# PWR_DC_DC_EXAR.net
KiCad netlist of a schematic drawn in Altium Designer
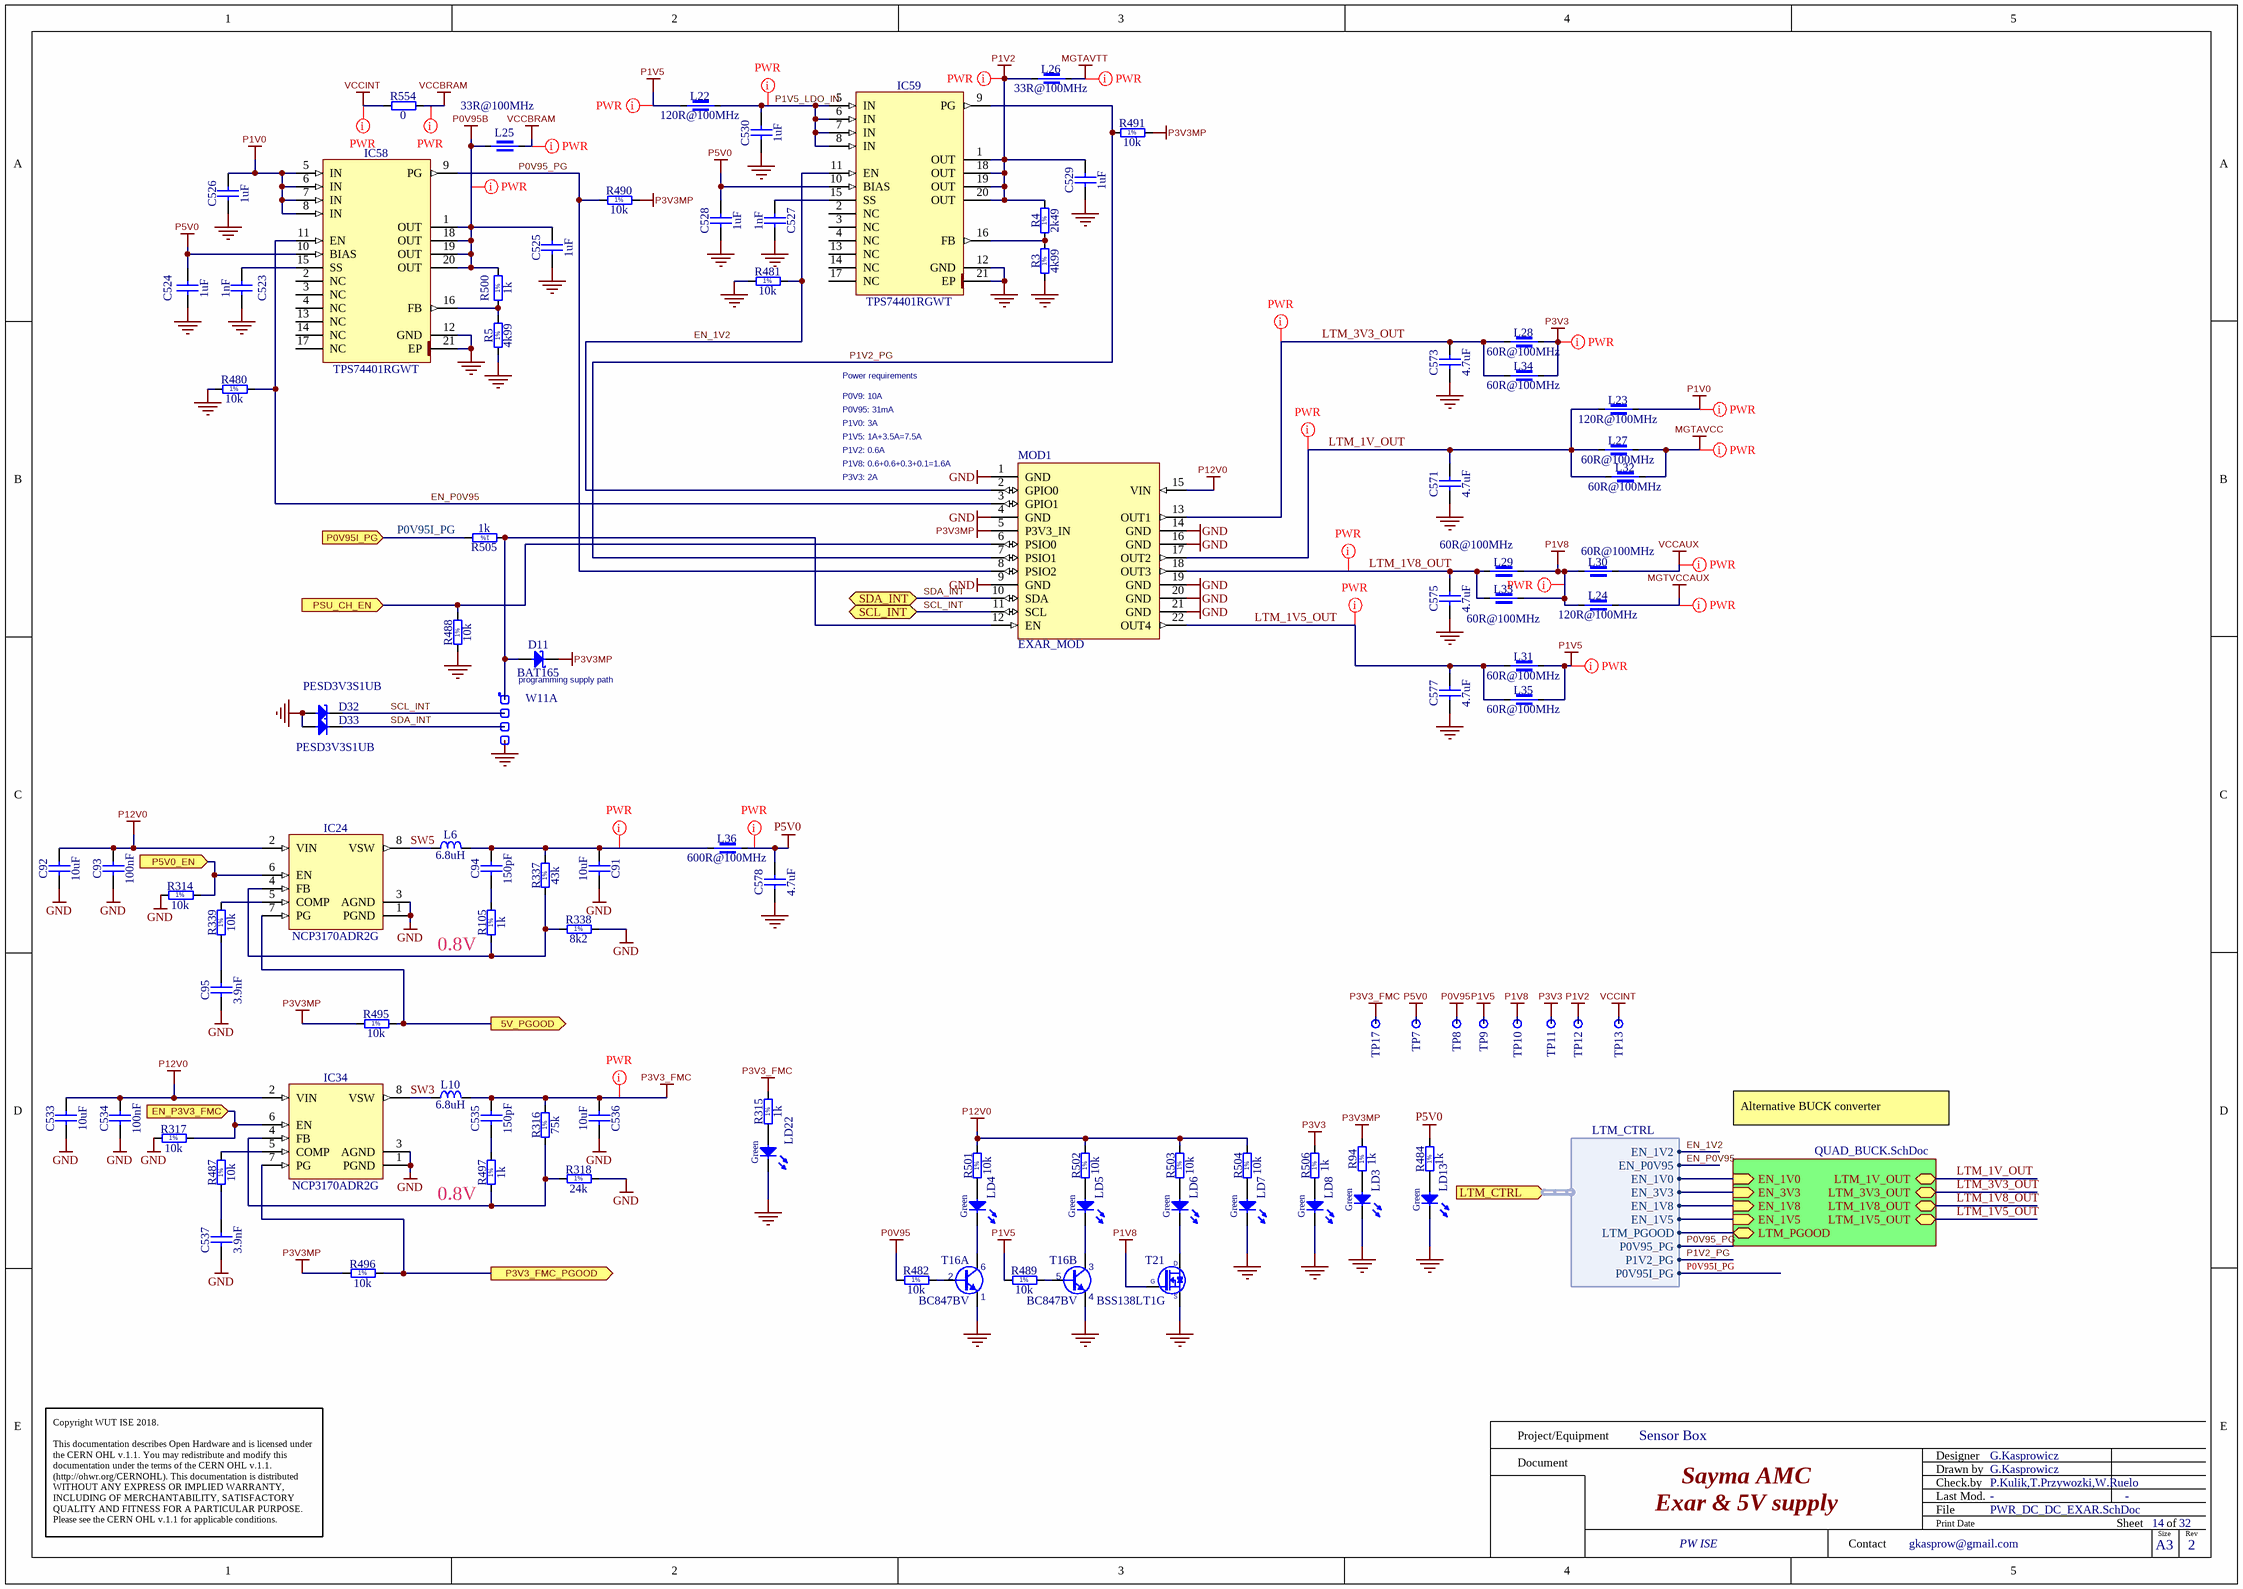
[diagram p0: PWR_DC_DC_EXAR.SchDoc]

(export (version "E")
  (design (tool "Eeschema 10.0.6"))
  (components
    (comp (ref "C91")
      (value "10uF")
      (footprint "CAPC2012X135N")
      (description "Non-polarised capacitor")
      (fields
        (field (name "PART NUMBER") "CC0805_10UF_16V_10%_X5R")
        (field (name "VOLTAGE") "16V")
        (field (name "AUTHOR") "CERN DEM JLC")
      )
      (libsource (lib "Capacitors") (part "Capacitor - non polarized"))
    )
    (comp (ref "C92")
      (value "10uF")
      (footprint "CAPC2012X135N")
      (description "Non-polarised capacitor")
      (fields
        (field (name "PART NUMBER") "CC0805_10UF_16V_10%_X5R")
        (field (name "VOLTAGE") "16V")
        (field (name "AUTHOR") "CERN DEM JLC")
      )
      (libsource (lib "Capacitors") (part "Capacitor - non polarized"))
    )
    (comp (ref "C93")
      (value "100nF")
      (footprint "CAPC1005X55N")
      (description "Non-polarised capacitor")
      (fields
        (field (name "PART NUMBER") "CC0402_100NF_16V_10%_X5R")
        (field (name "VOLTAGE") "16V")
        (field (name "AUTHOR") "CERN DEM JLC")
      )
      (libsource (lib "Capacitors") (part "Capacitor - non polarized"))
    )
    (comp (ref "C94")
      (value "150pF")
      (footprint "CAPC1608X87N")
      (description "Non-polarised capacitor")
      (fields
        (field (name "PART NUMBER") "CC0603_150PF_50V_1%_NP0")
        (field (name "VOLTAGE") "50V")
        (field (name "AUTHOR") "CERN DEM MR")
      )
      (libsource (lib "Capacitors") (part "Capacitor - non polarized"))
    )
    (comp (ref "C95")
      (value "3.9nF")
      (footprint "CAPC1608X87N")
      (description "Non-polarised capacitor")
      (fields
        (field (name "PART NUMBER") "CC0603_3.9NF_50V_5%_X7R")
        (field (name "VOLTAGE") "50V")
        (field (name "AUTHOR") "CERN DEM JLC")
      )
      (libsource (lib "Capacitors") (part "Capacitor - non polarized"))
    )
    (comp (ref "C523")
      (value "1nF")
      (footprint "CAPC1005X55N")
      (description "Non-polarised capacitor")
      (fields
        (field (name "MANUFACTURER PART NUMBER") "CC0402_1NF_50V_10%_X7R")
        (field (name "MANUFACTURER") "GENERIC")
        (field (name "AUTHOR") "CERN DEM JLC")
      )
      (libsource (lib "Capacitors") (part "Capacitor - non polarized"))
    )
    (comp (ref "C524")
      (value "1uF")
      (footprint "CAPC1005X55N")
      (description "Non-polarised capacitor")
      (fields
        (field (name "MANUFACTURER PART NUMBER") "CC0402_1UF_16V_10%_X5R")
        (field (name "MANUFACTURER") "GENERIC")
        (field (name "AUTHOR") "CERN DEM JLC")
      )
      (libsource (lib "Capacitors") (part "Capacitor - non polarized"))
    )
    (comp (ref "C525")
      (value "1uF")
      (footprint "CAPC1005X55N")
      (description "Non-polarised capacitor")
      (fields
        (field (name "MANUFACTURER PART NUMBER") "CC0402_1UF_16V_10%_X5R")
        (field (name "MANUFACTURER") "GENERIC")
        (field (name "AUTHOR") "CERN DEM JLC")
      )
      (libsource (lib "Capacitors") (part "Capacitor - non polarized"))
    )
    (comp (ref "C526")
      (value "1uF")
      (footprint "CAPC1005X55N")
      (description "Non-polarised capacitor")
      (fields
        (field (name "MANUFACTURER PART NUMBER") "CC0402_1UF_16V_10%_X5R")
        (field (name "MANUFACTURER") "GENERIC")
        (field (name "AUTHOR") "CERN DEM JLC")
      )
      (libsource (lib "Capacitors") (part "Capacitor - non polarized"))
    )
    (comp (ref "C527")
      (value "1nF")
      (footprint "CAPC1005X55N")
      (description "Non-polarised capacitor")
      (fields
        (field (name "MANUFACTURER PART NUMBER") "CC0402_1NF_50V_10%_X7R")
        (field (name "MANUFACTURER") "GENERIC")
        (field (name "AUTHOR") "CERN DEM JLC")
      )
      (libsource (lib "Capacitors") (part "Capacitor - non polarized"))
    )
    (comp (ref "C528")
      (value "1uF")
      (footprint "CAPC1005X55N")
      (description "Non-polarised capacitor")
      (fields
        (field (name "MANUFACTURER PART NUMBER") "CC0402_1UF_16V_10%_X5R")
        (field (name "MANUFACTURER") "GENERIC")
        (field (name "AUTHOR") "CERN DEM JLC")
      )
      (libsource (lib "Capacitors") (part "Capacitor - non polarized"))
    )
    (comp (ref "C529")
      (value "1uF")
      (footprint "CAPC1005X55N")
      (description "Non-polarised capacitor")
      (fields
        (field (name "MANUFACTURER PART NUMBER") "CC0402_1UF_16V_10%_X5R")
        (field (name "MANUFACTURER") "GENERIC")
        (field (name "AUTHOR") "CERN DEM JLC")
      )
      (libsource (lib "Capacitors") (part "Capacitor - non polarized"))
    )
    (comp (ref "C530")
      (value "1uF")
      (footprint "CAPC1005X55N")
      (description "Non-polarised capacitor")
      (fields
        (field (name "MANUFACTURER PART NUMBER") "CC0402_1UF_16V_10%_X5R")
        (field (name "MANUFACTURER") "GENERIC")
        (field (name "AUTHOR") "CERN DEM JLC")
      )
      (libsource (lib "Capacitors") (part "Capacitor - non polarized"))
    )
    (comp (ref "C533")
      (value "10uF")
      (footprint "CAPC2012X135N")
      (description "Non-polarised capacitor")
      (fields
        (field (name "PART NUMBER") "CC0805_10UF_16V_10%_X5R")
        (field (name "VOLTAGE") "16V")
        (field (name "AUTHOR") "CERN DEM JLC")
      )
      (libsource (lib "Capacitors") (part "Capacitor - non polarized"))
    )
    (comp (ref "C534")
      (value "100nF")
      (footprint "CAPC1005X55N")
      (description "Non-polarised capacitor")
      (fields
        (field (name "PART NUMBER") "CC0402_100NF_16V_10%_X5R")
        (field (name "VOLTAGE") "16V")
        (field (name "AUTHOR") "CERN DEM JLC")
      )
      (libsource (lib "Capacitors") (part "Capacitor - non polarized"))
    )
    (comp (ref "C535")
      (value "150pF")
      (footprint "CAPC1608X87N")
      (description "Non-polarised capacitor")
      (fields
        (field (name "PART NUMBER") "CC0603_150PF_50V_1%_NP0")
        (field (name "VOLTAGE") "50V")
        (field (name "AUTHOR") "CERN DEM MR")
      )
      (libsource (lib "Capacitors") (part "Capacitor - non polarized"))
    )
    (comp (ref "C536")
      (value "10uF")
      (footprint "CAPC2012X135N")
      (description "Non-polarised capacitor")
      (fields
        (field (name "PART NUMBER") "CC0805_10UF_16V_10%_X5R")
        (field (name "VOLTAGE") "16V")
        (field (name "AUTHOR") "CERN DEM JLC")
      )
      (libsource (lib "Capacitors") (part "Capacitor - non polarized"))
    )
    (comp (ref "C537")
      (value "3.9nF")
      (footprint "CAPC1608X87N")
      (description "Non-polarised capacitor")
      (fields
        (field (name "PART NUMBER") "CC0603_3.9NF_50V_5%_X7R")
        (field (name "VOLTAGE") "50V")
        (field (name "AUTHOR") "CERN DEM JLC")
      )
      (libsource (lib "Capacitors") (part "Capacitor - non polarized"))
    )
    (comp (ref "C571")
      (value "4.7uF")
      (footprint "CAPC1709X95N")
      (description "Non-polarised capacitor")
      (fields
        (field (name "MANUFACTURER PART NUMBER") "CC0603_4.7UF_16V_10%_X5R")
        (field (name "MANUFACTURER") "GENERIC")
        (field (name "AUTHOR") "CERN DEM JLC")
      )
      (libsource (lib "Capacitors") (part "Capacitor - non polarized"))
    )
    (comp (ref "C573")
      (value "4.7uF")
      (footprint "CAPC1709X95N")
      (description "Non-polarised capacitor")
      (fields
        (field (name "MANUFACTURER PART NUMBER") "CC0603_4.7UF_16V_10%_X5R")
        (field (name "MANUFACTURER") "GENERIC")
        (field (name "AUTHOR") "CERN DEM JLC")
      )
      (libsource (lib "Capacitors") (part "Capacitor - non polarized"))
    )
    (comp (ref "C575")
      (value "4.7uF")
      (footprint "CAPC1709X95N")
      (description "Non-polarised capacitor")
      (fields
        (field (name "MANUFACTURER PART NUMBER") "CC0603_4.7UF_16V_10%_X5R")
        (field (name "MANUFACTURER") "GENERIC")
        (field (name "AUTHOR") "CERN DEM JLC")
      )
      (libsource (lib "Capacitors") (part "Capacitor - non polarized"))
    )
    (comp (ref "C577")
      (value "4.7uF")
      (footprint "CAPC1709X95N")
      (description "Non-polarised capacitor")
      (fields
        (field (name "MANUFACTURER PART NUMBER") "CC0603_4.7UF_16V_10%_X5R")
        (field (name "MANUFACTURER") "GENERIC")
        (field (name "AUTHOR") "CERN DEM JLC")
      )
      (libsource (lib "Capacitors") (part "Capacitor - non polarized"))
    )
    (comp (ref "C578")
      (value "4.7uF")
      (footprint "CAPC1709X95N")
      (description "Non-polarised capacitor")
      (fields
        (field (name "MANUFACTURER PART NUMBER") "CC0603_4.7UF_16V_10%_X5R")
        (field (name "MANUFACTURER") "GENERIC")
        (field (name "AUTHOR") "CERN DEM JLC")
      )
      (libsource (lib "Capacitors") (part "Capacitor - non polarized"))
    )
    (comp (ref "D11")
      (value "BAT165")
      (footprint "SOD2512X110N")
      (description "Schottky Diode")
      (fields
        (field (name "MANUFACTURER") "INFINEON")
        (field (name "VOLTAGE") "40V")
        (field (name "AUTHOR") "CERN DEM JLC")
      )
      (libsource (lib "ICs And Semiconductors") (part "Diode Schottky"))
    )
    (comp (ref "D32")
      (value "PESD3V3S1UB")
      (footprint "SODFL1608X65N")
      (description "ESD protection diode")
      (fields
        (field (name "MANUFACTURER") "NXP SEMICONDUCTORS")
        (field (name "VOLTAGE") "3V3")
        (field (name "AUTHOR") "CERN DEM JLC")
      )
      (libsource (lib "ICs And Semiconductors") (part "Diode ESD"))
    )
    (comp (ref "D33")
      (value "PESD3V3S1UB")
      (footprint "SODFL1608X65N")
      (description "ESD protection diode")
      (fields
        (field (name "MANUFACTURER") "NXP SEMICONDUCTORS")
        (field (name "VOLTAGE") "3V3")
        (field (name "AUTHOR") "CERN DEM JLC")
      )
      (libsource (lib "ICs And Semiconductors") (part "Diode ESD"))
    )
    (comp (ref "IC24")
      (value "NCP3170ADR2G")
      (footprint "SOIC127P600X175-8N")
      (description "Synchronous PWM Switching Converter")
      (fields (field (name "MANUFACTURER") "ON SEMICONDUCTOR") (field (name "AUTHOR") "CERN DEM MR"))
      (libsource (lib "ICs And Semiconductors") (part "NCP3170ADR2G"))
    )
    (comp (ref "IC34")
      (value "NCP3170ADR2G")
      (footprint "SOIC127P600X175-8N")
      (description "Synchronous PWM Switching Converter")
      (fields (field (name "MANUFACTURER") "ON SEMICONDUCTOR") (field (name "AUTHOR") "CERN DEM MR"))
      (libsource (lib "ICs And Semiconductors") (part "NCP3170ADR2G"))
    )
    (comp (ref "IC58")
      (value "TPS74401RGWT")
      (footprint "QFN65P500X500X100-21N-S325")
      (description "Single Output LDO, 3.0A, Adj.(0.8 to 3.3V), Fast Transient Response, Programmable SoftStart")
      (fields (field (name "MANUFACTURER") "TEXAS INSTRUMENTS") (field (name "AUTHOR") "CERN DEM JLC"))
      (libsource (lib "ICs And Semiconductors") (part "TPS74401RGW"))
    )
    (comp (ref "IC59")
      (value "TPS74401RGWT")
      (footprint "QFN65P500X500X100-21N-S325")
      (description "Single Output LDO, 3.0A, Adj.(0.8 to 3.3V), Fast Transient Response, Programmable SoftStart")
      (fields (field (name "MANUFACTURER") "TEXAS INSTRUMENTS") (field (name "AUTHOR") "CERN DEM JLC"))
      (libsource (lib "ICs And Semiconductors") (part "TPS74401RGW"))
    )
    (comp (ref "L6")
      (value "6.8uH")
      (footprint "IND_BOURNS_SRU8043")
      (description "Inductor")
      (fields
        (field (name "PART NUMBER") "IND_6.8UH_30%_BOURNS_SRU8043")
        (field (name "POWER") "3.8A")
        (field (name "AUTHOR") "CERN DEM JMW")
      )
      (libsource (lib "Inductors & Transformers") (part "Inductor"))
    )
    (comp (ref "L10")
      (value "6.8uH")
      (footprint "IND_BOURNS_SRU8043")
      (description "Inductor")
      (fields
        (field (name "PART NUMBER") "IND_6.8UH_30%_BOURNS_SRU8043")
        (field (name "POWER") "3.8A")
        (field (name "AUTHOR") "CERN DEM JMW")
      )
      (libsource (lib "Inductors & Transformers") (part "Inductor"))
    )
    (comp (ref "L22")
      (value "120R@100MHz")
      (footprint "INDC1608X95N")
      (fields
        (field (name "MANUFACTURER PART NUMBER") "BLM18PG121SN1D")
        (field (name "MANUFACTURER") "MURATA")
        (field (name "PART NUMBER") "IND0603_MURATA_BLM18PG121SN1D")
        (field (name "AUTHOR") "CERN DEM BC")
      )
      (libsource (lib "") (part "Ferrite Bead_1"))
    )
    (comp (ref "L23")
      (value "120R@100MHz")
      (footprint "INDC1608X95N")
      (fields
        (field (name "MANUFACTURER PART NUMBER") "BLM18PG121SN1D")
        (field (name "MANUFACTURER") "MURATA")
        (field (name "PART NUMBER") "IND0603_MURATA_BLM18PG121SN1D")
        (field (name "AUTHOR") "CERN DEM BC")
      )
      (libsource (lib "") (part "Ferrite Bead_1"))
    )
    (comp (ref "L24")
      (value "120R@100MHz")
      (footprint "INDC1608X95N")
      (fields
        (field (name "MANUFACTURER PART NUMBER") "BLM18PG121SN1D")
        (field (name "MANUFACTURER") "MURATA")
        (field (name "PART NUMBER") "IND0603_MURATA_BLM18PG121SN1D")
        (field (name "AUTHOR") "CERN DEM BC")
      )
      (libsource (lib "") (part "Ferrite Bead_1"))
    )
    (comp (ref "L25")
      (value "33R@100MHz")
      (footprint "INDC1608X95N")
      (fields
        (field (name "MANUFACTURER PART NUMBER") "BLM18PG330SN1D")
        (field (name "MANUFACTURER") "MURATA")
        (field (name "PART NUMBER") "IND0603_MURATA_BLM18PG330SN1D")
        (field (name "AUTHOR") "CERN DEM JMW")
      )
      (libsource (lib "Inductors & Transformers") (part "Ferrite Bead"))
    )
    (comp (ref "L26")
      (value "33R@100MHz")
      (footprint "INDC1608X95N")
      (fields
        (field (name "MANUFACTURER PART NUMBER") "BLM18PG330SN1D")
        (field (name "MANUFACTURER") "MURATA")
        (field (name "PART NUMBER") "IND0603_MURATA_BLM18PG330SN1D")
        (field (name "AUTHOR") "CERN DEM JMW")
      )
      (libsource (lib "Inductors & Transformers") (part "Ferrite Bead"))
    )
    (comp (ref "L27")
      (value "60R@100MHz")
      (footprint "INDC4516X180N")
      (fields
        (field (name "MANUFACTURER PART NUMBER") "BLM41PG600SN1L")
        (field (name "MANUFACTURER") "MURATA")
        (field (name "PART NUMBER") "IND1806_MURATA_BLM41PG600SN1L")
        (field (name "AUTHOR") "CERN DEM JLC")
      )
      (libsource (lib "Inductors & Transformers") (part "Ferrite Bead"))
    )
    (comp (ref "L28")
      (value "60R@100MHz")
      (footprint "INDC4516X180N")
      (fields
        (field (name "MANUFACTURER PART NUMBER") "BLM41PG600SN1L")
        (field (name "MANUFACTURER") "MURATA")
        (field (name "PART NUMBER") "IND1806_MURATA_BLM41PG600SN1L")
        (field (name "AUTHOR") "CERN DEM JLC")
      )
      (libsource (lib "Inductors & Transformers") (part "Ferrite Bead"))
    )
    (comp (ref "L29")
      (value "60R@100MHz")
      (footprint "INDC4516X180N")
      (fields
        (field (name "MANUFACTURER PART NUMBER") "BLM41PG600SN1L")
        (field (name "MANUFACTURER") "MURATA")
        (field (name "PART NUMBER") "IND1806_MURATA_BLM41PG600SN1L")
        (field (name "AUTHOR") "CERN DEM JLC")
      )
      (libsource (lib "Inductors & Transformers") (part "Ferrite Bead"))
    )
    (comp (ref "L30")
      (value "60R@100MHz")
      (footprint "INDC4516X180N")
      (fields
        (field (name "MANUFACTURER PART NUMBER") "BLM41PG600SN1L")
        (field (name "MANUFACTURER") "MURATA")
        (field (name "PART NUMBER") "IND1806_MURATA_BLM41PG600SN1L")
        (field (name "AUTHOR") "CERN DEM JLC")
      )
      (libsource (lib "Inductors & Transformers") (part "Ferrite Bead"))
    )
    (comp (ref "L31")
      (value "60R@100MHz")
      (footprint "INDC4516X180N")
      (fields
        (field (name "MANUFACTURER PART NUMBER") "BLM41PG600SN1L")
        (field (name "MANUFACTURER") "MURATA")
        (field (name "PART NUMBER") "IND1806_MURATA_BLM41PG600SN1L")
        (field (name "AUTHOR") "CERN DEM JLC")
      )
      (libsource (lib "Inductors & Transformers") (part "Ferrite Bead"))
    )
    (comp (ref "L32")
      (value "60R@100MHz")
      (footprint "INDC4516X180N")
      (fields
        (field (name "MANUFACTURER PART NUMBER") "BLM41PG600SN1L")
        (field (name "MANUFACTURER") "MURATA")
        (field (name "PART NUMBER") "IND1806_MURATA_BLM41PG600SN1L")
        (field (name "AUTHOR") "CERN DEM JLC")
      )
      (libsource (lib "Inductors & Transformers") (part "Ferrite Bead"))
    )
    (comp (ref "L33")
      (value "60R@100MHz")
      (footprint "INDC4516X180N")
      (fields
        (field (name "MANUFACTURER PART NUMBER") "BLM41PG600SN1L")
        (field (name "MANUFACTURER") "MURATA")
        (field (name "PART NUMBER") "IND1806_MURATA_BLM41PG600SN1L")
        (field (name "AUTHOR") "CERN DEM JLC")
      )
      (libsource (lib "Inductors & Transformers") (part "Ferrite Bead"))
    )
    (comp (ref "L34")
      (value "60R@100MHz")
      (footprint "INDC4516X180N")
      (fields
        (field (name "MANUFACTURER PART NUMBER") "BLM41PG600SN1L")
        (field (name "MANUFACTURER") "MURATA")
        (field (name "PART NUMBER") "IND1806_MURATA_BLM41PG600SN1L")
        (field (name "AUTHOR") "CERN DEM JLC")
      )
      (libsource (lib "Inductors & Transformers") (part "Ferrite Bead"))
    )
    (comp (ref "L35")
      (value "60R@100MHz")
      (footprint "INDC4516X180N")
      (fields
        (field (name "MANUFACTURER PART NUMBER") "BLM41PG600SN1L")
        (field (name "MANUFACTURER") "MURATA")
        (field (name "PART NUMBER") "IND1806_MURATA_BLM41PG600SN1L")
        (field (name "AUTHOR") "CERN DEM JLC")
      )
      (libsource (lib "Inductors & Transformers") (part "Ferrite Bead"))
    )
    (comp (ref "L36")
      (value "600R@100MHz")
      (footprint "INDC2012X110N")
      (fields
        (field (name "MANUFACTURER PART NUMBER") "742792040")
        (field (name "MANUFACTURER") "WURTH ELEKTRONIK")
        (field (name "PART NUMBER") "IND0805_WURTH_742792040")
        (field (name "AUTHOR") "CERN DEM JLC")
      )
      (libsource (lib "Inductors & Transformers") (part "Ferrite Bead"))
    )
    (comp (ref "LD3")
      (value "Green")
      (footprint "LED_KINGBRIGHT_KPH-1608CGCK")
      (description "LED Green 1C 2A")
      (fields
        (field (name "MANUFACTURER PART NUMBER") "KPH-1608CGCK")
        (field (name "MANUFACTURER") "KINGBRIGHT")
        (field (name "AUTHOR") "CERN DEM JLC")
      )
      (libsource (lib "ICs And Semiconductors") (part "LED Green 1C 2A"))
    )
    (comp (ref "LD4")
      (value "Green")
      (footprint "LED_KINGBRIGHT_KPH-1608CGCK")
      (description "LED Green 1C 2A")
      (fields
        (field (name "MANUFACTURER PART NUMBER") "KPH-1608CGCK")
        (field (name "MANUFACTURER") "KINGBRIGHT")
        (field (name "AUTHOR") "CERN DEM JLC")
      )
      (libsource (lib "ICs And Semiconductors") (part "LED Green 1C 2A"))
    )
    (comp (ref "LD5")
      (value "Green")
      (footprint "LED_KINGBRIGHT_KPH-1608CGCK")
      (description "LED Green 1C 2A")
      (fields
        (field (name "MANUFACTURER PART NUMBER") "KPH-1608CGCK")
        (field (name "MANUFACTURER") "KINGBRIGHT")
        (field (name "AUTHOR") "CERN DEM JLC")
      )
      (libsource (lib "ICs And Semiconductors") (part "LED Green 1C 2A"))
    )
    (comp (ref "LD6")
      (value "Green")
      (footprint "LED_KINGBRIGHT_KPH-1608CGCK")
      (description "LED Green 1C 2A")
      (fields
        (field (name "MANUFACTURER PART NUMBER") "KPH-1608CGCK")
        (field (name "MANUFACTURER") "KINGBRIGHT")
        (field (name "AUTHOR") "CERN DEM JLC")
      )
      (libsource (lib "ICs And Semiconductors") (part "LED Green 1C 2A"))
    )
    (comp (ref "LD7")
      (value "Green")
      (footprint "LED_KINGBRIGHT_KPH-1608CGCK")
      (description "LED Green 1C 2A")
      (fields
        (field (name "MANUFACTURER PART NUMBER") "KPH-1608CGCK")
        (field (name "MANUFACTURER") "KINGBRIGHT")
        (field (name "AUTHOR") "CERN DEM JLC")
      )
      (libsource (lib "ICs And Semiconductors") (part "LED Green 1C 2A"))
    )
    (comp (ref "LD8")
      (value "Green")
      (footprint "LED_KINGBRIGHT_KPH-1608CGCK")
      (description "LED Green 1C 2A")
      (fields
        (field (name "MANUFACTURER PART NUMBER") "KPH-1608CGCK")
        (field (name "MANUFACTURER") "KINGBRIGHT")
        (field (name "AUTHOR") "CERN DEM JLC")
      )
      (libsource (lib "ICs And Semiconductors") (part "LED Green 1C 2A"))
    )
    (comp (ref "LD13")
      (value "Green")
      (footprint "LED_KINGBRIGHT_KPH-1608CGCK")
      (description "LED Green 1C 2A")
      (fields
        (field (name "MANUFACTURER PART NUMBER") "KPH-1608CGCK")
        (field (name "MANUFACTURER") "KINGBRIGHT")
        (field (name "AUTHOR") "CERN DEM JLC")
      )
      (libsource (lib "ICs And Semiconductors") (part "LED Green 1C 2A"))
    )
    (comp (ref "LD22")
      (value "Green")
      (footprint "LED_KINGBRIGHT_KPH-1608CGCK")
      (description "LED Green 1C 2A")
      (fields
        (field (name "MANUFACTURER PART NUMBER") "KPH-1608CGCK")
        (field (name "MANUFACTURER") "KINGBRIGHT")
        (field (name "AUTHOR") "CERN DEM JLC")
      )
      (libsource (lib "ICs And Semiconductors") (part "LED Green 1C 2A"))
    )
    (comp (ref "MOD1")
      (value "EXAR_MOD")
      (footprint "EXAR_MOD")
      (description "4 channel PCB module based on XRP7724ILB-F")
      (libsource (lib "LIBRARY_SCH") (part "DC/DC_EXAR_MOD"))
    )
    (comp (ref "R3")
      (value "4k99")
      (footprint "RESC1608X55N")
      (description "Resistor - 1%")
      (fields
        (field (name "MANUFACTURER PART NUMBER") "R0603_4K99_1%_0.063W_50PPM")
        (field (name "MANUFACTURER") "GENERIC")
        (field (name "AUTHOR") "CERN DEM JLC")
      )
      (libsource (lib "Resistors") (part "Resistor - 1%"))
    )
    (comp (ref "R4")
      (value "2k49")
      (footprint "RESC1608X55N")
      (description "Resistor - 1%")
      (fields
        (field (name "MANUFACTURER PART NUMBER") "R0603_2K49_1%_0.063W_50PPM")
        (field (name "MANUFACTURER") "GENERIC")
        (field (name "AUTHOR") "CERN DEM JLC")
      )
      (libsource (lib "Resistors") (part "Resistor - 1%"))
    )
    (comp (ref "R5")
      (value "4k99")
      (footprint "RESC1608X55N")
      (description "Resistor - 1%")
      (fields
        (field (name "MANUFACTURER PART NUMBER") "R0603_4K99_1%_0.063W_50PPM")
        (field (name "MANUFACTURER") "GENERIC")
        (field (name "AUTHOR") "CERN DEM JLC")
      )
      (libsource (lib "Resistors") (part "Resistor - 1%"))
    )
    (comp (ref "R94")
      (value "1k")
      (footprint "RESC1005X40N")
      (description "Resistor - 1%")
      (fields
        (field (name "MANUFACTURER PART NUMBER") "R0402_1K_1%_0.0625W_100PPM")
        (field (name "MANUFACTURER") "GENERIC")
        (field (name "AUTHOR") "CERN DEM JLC")
      )
      (libsource (lib "Resistors") (part "Resistor - 1%"))
    )
    (comp (ref "R105")
      (value "1k")
      (footprint "RESC1005X40N")
      (description "Resistor - 1%")
      (fields
        (field (name "PART NUMBER") "R0402_1K_1%_0.0625W_100PPM")
        (field (name "POWER") "0.0625W")
        (field (name "AUTHOR") "CERN DEM JLC")
      )
      (libsource (lib "Resistors") (part "Resistor - 1%"))
    )
    (comp (ref "R314")
      (value "10k")
      (footprint "RESC1005X40N")
      (description "Resistor - 1%")
      (fields
        (field (name "MANUFACTURER PART NUMBER") "R0402_10K_1%_0.0625W_100PPM")
        (field (name "MANUFACTURER") "GENERIC")
        (field (name "AUTHOR") "CERN DEM JLC")
      )
      (libsource (lib "Resistors") (part "Resistor - 1%"))
    )
    (comp (ref "R315")
      (value "1k")
      (footprint "RESC1005X40N")
      (description "Resistor - 1%")
      (fields
        (field (name "MANUFACTURER PART NUMBER") "R0402_1K_1%_0.0625W_100PPM")
        (field (name "MANUFACTURER") "GENERIC")
        (field (name "AUTHOR") "CERN DEM JLC")
      )
      (libsource (lib "Resistors") (part "Resistor - 1%"))
    )
    (comp (ref "R316")
      (value "75k")
      (footprint "RESC1608X55N")
      (description "Resistor - 1%")
      (fields
        (field (name "PART NUMBER") "R0603_75K_1%_0.1W_100PPM")
        (field (name "POWER") "0.1W")
        (field (name "AUTHOR") "CERN DEM JLC")
      )
      (libsource (lib "Resistors") (part "Resistor - 1%"))
    )
    (comp (ref "R317")
      (value "10k")
      (footprint "RESC1005X40N")
      (description "Resistor - 1%")
      (fields
        (field (name "MANUFACTURER PART NUMBER") "R0402_10K_1%_0.0625W_100PPM")
        (field (name "MANUFACTURER") "GENERIC")
        (field (name "AUTHOR") "CERN DEM JLC")
      )
      (libsource (lib "Resistors") (part "Resistor - 1%"))
    )
    (comp (ref "R318")
      (value "24k")
      (footprint "RESC1608X55N")
      (description "Resistor - 1%")
      (fields
        (field (name "PART NUMBER") "R0603_24K_1%_0.1W_100PPM")
        (field (name "POWER") "0.1W")
        (field (name "AUTHOR") "CERN DEM JLC")
      )
      (libsource (lib "Resistors") (part "Resistor - 1%"))
    )
    (comp (ref "R337")
      (value "43k")
      (footprint "RESC1608X55N")
      (description "Resistor - 1%")
      (fields
        (field (name "PART NUMBER") "R0603_43K_1%_0.1W_100PPM")
        (field (name "POWER") "0.1W")
        (field (name "AUTHOR") "CERN DEM JLC")
      )
      (libsource (lib "Resistors") (part "Resistor - 1%"))
    )
    (comp (ref "R338")
      (value "8k2")
      (footprint "RESC1608X55N")
      (description "Resistor - 1%")
      (fields
        (field (name "PART NUMBER") "R0603_8K2_1%_0.1W_100PPM")
        (field (name "POWER") "0.1W")
        (field (name "AUTHOR") "CERN DEM JLC")
      )
      (libsource (lib "Resistors") (part "Resistor - 1%"))
    )
    (comp (ref "R339")
      (value "10k")
      (footprint "RESC1005X40N")
      (description "Resistor - 1%")
      (fields
        (field (name "PART NUMBER") "R0402_10K_1%_0.0625W_100PPM")
        (field (name "POWER") "0.0625W")
        (field (name "AUTHOR") "CERN DEM JLC")
      )
      (libsource (lib "Resistors") (part "Resistor - 1%"))
    )
    (comp (ref "R480")
      (value "10k")
      (footprint "RESC1005X40N")
      (description "Resistor - 1%")
      (fields
        (field (name "MANUFACTURER PART NUMBER") "R0402_10K_1%_0.0625W_100PPM")
        (field (name "MANUFACTURER") "GENERIC")
        (field (name "AUTHOR") "CERN DEM JLC")
      )
      (libsource (lib "Resistors") (part "Resistor - 1%"))
    )
    (comp (ref "R481")
      (value "10k")
      (footprint "RESC1005X40N")
      (description "Resistor - 1%")
      (fields
        (field (name "MANUFACTURER PART NUMBER") "R0402_10K_1%_0.0625W_100PPM")
        (field (name "MANUFACTURER") "GENERIC")
        (field (name "AUTHOR") "CERN DEM JLC")
      )
      (libsource (lib "Resistors") (part "Resistor - 1%"))
    )
    (comp (ref "R482")
      (value "10k")
      (footprint "RESC1005X40N")
      (description "Resistor - 1%")
      (fields
        (field (name "MANUFACTURER PART NUMBER") "R0402_10K_1%_0.0625W_100PPM")
        (field (name "MANUFACTURER") "GENERIC")
        (field (name "AUTHOR") "CERN DEM JLC")
      )
      (libsource (lib "Resistors") (part "Resistor - 1%"))
    )
    (comp (ref "R484")
      (value "1k")
      (footprint "RESC1005X40N")
      (description "Resistor - 1%")
      (fields
        (field (name "MANUFACTURER PART NUMBER") "R0402_1K_1%_0.0625W_100PPM")
        (field (name "MANUFACTURER") "GENERIC")
        (field (name "AUTHOR") "CERN DEM JLC")
      )
      (libsource (lib "Resistors") (part "Resistor - 1%"))
    )
    (comp (ref "R487")
      (value "10k")
      (footprint "RESC1005X40N")
      (description "Resistor - 1%")
      (fields
        (field (name "PART NUMBER") "R0402_10K_1%_0.0625W_100PPM")
        (field (name "POWER") "0.0625W")
        (field (name "AUTHOR") "CERN DEM JLC")
      )
      (libsource (lib "Resistors") (part "Resistor - 1%"))
    )
    (comp (ref "R488")
      (value "10k")
      (footprint "RESC1005X40N")
      (description "Resistor - 1%")
      (fields
        (field (name "MANUFACTURER PART NUMBER") "R0402_10K_1%_0.0625W_100PPM")
        (field (name "MANUFACTURER") "GENERIC")
        (field (name "AUTHOR") "CERN DEM JLC")
      )
      (libsource (lib "Resistors") (part "Resistor - 1%"))
    )
    (comp (ref "R489")
      (value "10k")
      (footprint "RESC1005X40N")
      (description "Resistor - 1%")
      (fields
        (field (name "MANUFACTURER PART NUMBER") "R0402_10K_1%_0.0625W_100PPM")
        (field (name "MANUFACTURER") "GENERIC")
        (field (name "AUTHOR") "CERN DEM JLC")
      )
      (libsource (lib "Resistors") (part "Resistor - 1%"))
    )
    (comp (ref "R490")
      (value "10k")
      (footprint "RESC1005X40N")
      (description "Resistor - 1%")
      (fields
        (field (name "MANUFACTURER PART NUMBER") "R0402_10K_1%_0.0625W_100PPM")
        (field (name "MANUFACTURER") "GENERIC")
        (field (name "AUTHOR") "CERN DEM JLC")
      )
      (libsource (lib "Resistors") (part "Resistor - 1%"))
    )
    (comp (ref "R491")
      (value "10k")
      (footprint "RESC1005X40N")
      (description "Resistor - 1%")
      (fields
        (field (name "MANUFACTURER PART NUMBER") "R0402_10K_1%_0.0625W_100PPM")
        (field (name "MANUFACTURER") "GENERIC")
        (field (name "AUTHOR") "CERN DEM JLC")
      )
      (libsource (lib "Resistors") (part "Resistor - 1%"))
    )
    (comp (ref "R495")
      (value "10k")
      (footprint "RESC1005X40N")
      (description "Resistor - 1%")
      (fields
        (field (name "MANUFACTURER PART NUMBER") "R0402_10K_1%_0.0625W_100PPM")
        (field (name "MANUFACTURER") "GENERIC")
        (field (name "AUTHOR") "CERN DEM JLC")
      )
      (libsource (lib "Resistors") (part "Resistor - 1%"))
    )
    (comp (ref "R496")
      (value "10k")
      (footprint "RESC1005X40N")
      (description "Resistor - 1%")
      (fields
        (field (name "MANUFACTURER PART NUMBER") "R0402_10K_1%_0.0625W_100PPM")
        (field (name "MANUFACTURER") "GENERIC")
        (field (name "AUTHOR") "CERN DEM JLC")
      )
      (libsource (lib "Resistors") (part "Resistor - 1%"))
    )
    (comp (ref "R497")
      (value "1k")
      (footprint "RESC1005X40N")
      (description "Resistor - 1%")
      (fields
        (field (name "PART NUMBER") "R0402_1K_1%_0.0625W_100PPM")
        (field (name "POWER") "0.0625W")
        (field (name "AUTHOR") "CERN DEM JLC")
      )
      (libsource (lib "Resistors") (part "Resistor - 1%"))
    )
    (comp (ref "R500")
      (value "1k")
      (footprint "RESC1005X40N")
      (description "Resistor - 1%")
      (fields
        (field (name "MANUFACTURER PART NUMBER") "R0402_1K_1%_0.0625W_100PPM")
        (field (name "MANUFACTURER") "GENERIC")
        (field (name "AUTHOR") "CERN DEM JLC")
      )
      (libsource (lib "Resistors") (part "Resistor - 1%"))
    )
    (comp (ref "R501")
      (value "10k")
      (footprint "RESC1005X40N")
      (description "Resistor - 1%")
      (fields
        (field (name "MANUFACTURER PART NUMBER") "R0402_10K_1%_0.0625W_100PPM")
        (field (name "MANUFACTURER") "GENERIC")
        (field (name "AUTHOR") "CERN DEM JLC")
      )
      (libsource (lib "Resistors") (part "Resistor - 1%"))
    )
    (comp (ref "R502")
      (value "10k")
      (footprint "RESC1005X40N")
      (description "Resistor - 1%")
      (fields
        (field (name "MANUFACTURER PART NUMBER") "R0402_10K_1%_0.0625W_100PPM")
        (field (name "MANUFACTURER") "GENERIC")
        (field (name "AUTHOR") "CERN DEM JLC")
      )
      (libsource (lib "Resistors") (part "Resistor - 1%"))
    )
    (comp (ref "R503")
      (value "10k")
      (footprint "RESC1005X40N")
      (description "Resistor - 1%")
      (fields
        (field (name "MANUFACTURER PART NUMBER") "R0402_10K_1%_0.0625W_100PPM")
        (field (name "MANUFACTURER") "GENERIC")
        (field (name "AUTHOR") "CERN DEM JLC")
      )
      (libsource (lib "Resistors") (part "Resistor - 1%"))
    )
    (comp (ref "R504")
      (value "10k")
      (footprint "RESC1005X40N")
      (description "Resistor - 1%")
      (fields
        (field (name "MANUFACTURER PART NUMBER") "R0402_10K_1%_0.0625W_100PPM")
        (field (name "MANUFACTURER") "GENERIC")
        (field (name "AUTHOR") "CERN DEM JLC")
      )
      (libsource (lib "Resistors") (part "Resistor - 1%"))
    )
    (comp (ref "R505")
      (value "1k")
      (footprint "RESC1005X40N")
      (description "Resistor - 1%")
      (fields
        (field (name "MANUFACTURER PART NUMBER") "R0402_1K_1%_0.0625W_100PPM")
        (field (name "MANUFACTURER") "GENERIC")
        (field (name "AUTHOR") "CERN DEM JLC")
      )
      (libsource (lib "Resistors") (part "Resistor - 1%"))
    )
    (comp (ref "R506")
      (value "1k")
      (footprint "RESC1005X40N")
      (description "Resistor - 1%")
      (fields
        (field (name "MANUFACTURER PART NUMBER") "R0402_1K_1%_0.0625W_100PPM")
        (field (name "MANUFACTURER") "GENERIC")
        (field (name "AUTHOR") "CERN DEM JLC")
      )
      (libsource (lib "Resistors") (part "Resistor - 1%"))
    )
    (comp (ref "R554")
      (value "0")
      (footprint "RESC2012X60N")
      (description "Resistor")
      (fields
        (field (name "PART NUMBER") "R0805_0R_JUMPER")
        (field (name "MANUFACTURER") "GENERIC")
        (field (name "AUTHOR") "CERN DEM JLC")
      )
      (libsource (lib "Resistors") (part "Resistor"))
    )
    (comp (ref "T16")
      (value "BC847BV")
      (footprint "SOTFL50P160X60-6N")
      (description "45V, 100mA NPN General Purpose Double Transistor")
      (fields (field (name "MANUFACTURER") "NXP SEMICONDUCTORS") (field (name "AUTHOR") "CERN DEM JLC"))
      (libsource (lib "ICs And Semiconductors") (part "BC847BV"))
    )
    (comp (ref "T21")
      (value "BSS138LT1G")
      (footprint "SOT95P240X110-3N")
      (description "N-CHANNEL MOSFET WITH DIODE")
      (fields (field (name "MANUFACTURER") "ON SEMICONDUCTOR") (field (name "AUTHOR") "CERN DEM JLC"))
      (libsource (lib "ICs And Semiconductors") (part "N-MOSFET-D 1G 2S 3D"))
    )
    (comp (ref "TP7")
      (value "Test Point")
      (footprint "TPS127")
      (fields (field (name "PART NUMBER") "SMD_PAD_1.27X1.27MM") (field (name "AUTHOR") "CERN DEM JLC"))
      (libsource (lib "Eletro-mechanical") (part "Test Point"))
    )
    (comp (ref "TP8")
      (value "Test Point")
      (footprint "TPS127")
      (fields (field (name "PART NUMBER") "SMD_PAD_1.27X1.27MM") (field (name "AUTHOR") "CERN DEM JLC"))
      (libsource (lib "Eletro-mechanical") (part "Test Point"))
    )
    (comp (ref "TP9")
      (value "Test Point")
      (footprint "TPS127")
      (fields (field (name "PART NUMBER") "SMD_PAD_1.27X1.27MM") (field (name "AUTHOR") "CERN DEM JLC"))
      (libsource (lib "Eletro-mechanical") (part "Test Point"))
    )
    (comp (ref "TP10")
      (value "Test Point")
      (footprint "TPS127")
      (fields (field (name "PART NUMBER") "SMD_PAD_1.27X1.27MM") (field (name "AUTHOR") "CERN DEM JLC"))
      (libsource (lib "Eletro-mechanical") (part "Test Point"))
    )
    (comp (ref "TP11")
      (value "Test Point")
      (footprint "TPS127")
      (fields (field (name "PART NUMBER") "SMD_PAD_1.27X1.27MM") (field (name "AUTHOR") "CERN DEM JLC"))
      (libsource (lib "Eletro-mechanical") (part "Test Point"))
    )
    (comp (ref "TP12")
      (value "Test Point")
      (footprint "TPS127")
      (fields (field (name "PART NUMBER") "SMD_PAD_1.27X1.27MM") (field (name "AUTHOR") "CERN DEM JLC"))
      (libsource (lib "Eletro-mechanical") (part "Test Point"))
    )
    (comp (ref "TP13")
      (value "Test Point")
      (footprint "TPS127")
      (fields (field (name "PART NUMBER") "SMD_PAD_1.27X1.27MM") (field (name "AUTHOR") "CERN DEM JLC"))
      (libsource (lib "Eletro-mechanical") (part "Test Point"))
    )
    (comp (ref "TP17")
      (value "Test Point")
      (footprint "TPS127")
      (fields (field (name "PART NUMBER") "SMD_PAD_1.27X1.27MM") (field (name "AUTHOR") "CERN DEM JLC"))
      (libsource (lib "Eletro-mechanical") (part "Test Point"))
    )
    (comp (ref "W11")
      (value "Header 4")
      (footprint "SAMTEC_MTLW-104-07-L-S-250")
      (description "4 Mini Wire-Wrap Contact Strip Header")
      (fields
        (field (name "MANUFACTURER PART NUMBER") "MTLW-104-07-L-S-250")
        (field (name "MANUFACTURER") "SAMTEC")
        (field (name "AUTHOR") "CERN DEM JLC")
      )
      (libsource (lib "Connectors") (part "Wire-Wrap Contact x4"))
    )
  )
  (nets
    (net (code "2") (name "/5V_PGOOD") (class "Default")
      (node (ref "IC24") (pin "7") (pinfunction "PG_7") (pintype "input"))
      (node (ref "R495") (pin "2") (pinfunction "2_2") (pintype "passive"))
    )
    (net (code "4") (name "/EN_1V2") (class "Default")
      (node (ref "IC59") (pin "11") (pinfunction "EN_11") (pintype "input"))
      (node (ref "MOD1") (pin "2") (pinfunction "GPIO0_2") (pintype "bidirectional"))
      (node (ref "R481") (pin "2") (pinfunction "2_2") (pintype "passive"))
    )
    (net (code "8") (name "/EN_P0V95") (class "Default")
      (node (ref "IC58") (pin "11") (pinfunction "EN_11") (pintype "input"))
      (node (ref "MOD1") (pin "3") (pinfunction "GPIO1_3") (pintype "bidirectional"))
      (node (ref "R480") (pin "2") (pinfunction "2_2") (pintype "passive"))
    )
    (net (code "9") (name "/EN_P3V3_FMC") (class "Default")
      (node (ref "IC34") (pin "6") (pinfunction "EN_6") (pintype "input"))
      (node (ref "R317") (pin "2") (pinfunction "2_2") (pintype "passive"))
    )
    (net (code "10") (name "/LTM_1V5_OUT") (class "Default")
      (node (ref "C577") (pin "2") (pinfunction "2_2") (pintype "passive"))
      (node (ref "L31") (pin "1") (pinfunction "1_1") (pintype "passive"))
      (node (ref "L35") (pin "1") (pinfunction "1_1") (pintype "passive"))
      (node (ref "MOD1") (pin "22") (pinfunction "OUT4_22") (pintype "output"))
    )
    (net (code "11") (name "/LTM_1V8_OUT") (class "Default")
      (node (ref "C575") (pin "2") (pinfunction "2_2") (pintype "passive"))
      (node (ref "L29") (pin "1") (pinfunction "1_1") (pintype "passive"))
      (node (ref "L33") (pin "1") (pinfunction "1_1") (pintype "passive"))
      (node (ref "MOD1") (pin "18") (pinfunction "OUT3_18") (pintype "output"))
    )
    (net (code "12") (name "/LTM_1V_OUT") (class "Default")
      (node (ref "C571") (pin "2") (pinfunction "2_2") (pintype "passive"))
      (node (ref "L23") (pin "2") (pinfunction "2_2") (pintype "passive"))
      (node (ref "L27") (pin "1") (pinfunction "1_1") (pintype "passive"))
      (node (ref "L32") (pin "1") (pinfunction "1_1") (pintype "passive"))
      (node (ref "MOD1") (pin "17") (pinfunction "OUT2_17") (pintype "output"))
    )
    (net (code "13") (name "/LTM_3V3_OUT") (class "Default")
      (node (ref "C573") (pin "2") (pinfunction "2_2") (pintype "passive"))
      (node (ref "L28") (pin "1") (pinfunction "1_1") (pintype "passive"))
      (node (ref "L34") (pin "1") (pinfunction "1_1") (pintype "passive"))
      (node (ref "MOD1") (pin "13") (pinfunction "OUT1_13") (pintype "output"))
    )
    (net (code "15") (name "/P0V95I_PG") (class "Default")
      (node (ref "R505") (pin "2") (pinfunction "2_2") (pintype "passive"))
    )
    (net (code "16") (name "/P0V95_PG") (class "Default")
      (node (ref "IC58") (pin "9") (pinfunction "PG_9") (pintype "output"))
      (node (ref "MOD1") (pin "8") (pinfunction "PSIO2_8") (pintype "bidirectional"))
      (node (ref "R490") (pin "1") (pinfunction "1_1") (pintype "passive"))
    )
    (net (code "17") (name "/P1V2_PG") (class "Default")
      (node (ref "IC59") (pin "9") (pinfunction "PG_9") (pintype "output"))
      (node (ref "MOD1") (pin "7") (pinfunction "PSIO1_7") (pintype "bidirectional"))
      (node (ref "R491") (pin "1") (pinfunction "1_1") (pintype "passive"))
    )
    (net (code "18") (name "/P1V5_LDO_IN") (class "Default")
      (node (ref "C530") (pin "2") (pinfunction "2_2") (pintype "passive"))
      (node (ref "IC59") (pin "5") (pinfunction "IN_5") (pintype "input"))
      (node (ref "IC59") (pin "6") (pinfunction "IN_6") (pintype "input"))
      (node (ref "IC59") (pin "7") (pinfunction "IN_7") (pintype "input"))
      (node (ref "IC59") (pin "8") (pinfunction "IN_8") (pintype "input"))
      (node (ref "L22") (pin "1") (pinfunction "1_1") (pintype "passive"))
    )
    (net (code "19") (name "/P3V3_FMC_PGOOD") (class "Default")
      (node (ref "IC34") (pin "7") (pinfunction "PG_7") (pintype "input"))
      (node (ref "R496") (pin "2") (pinfunction "2_2") (pintype "passive"))
    )
    (net (code "20") (name "/P5V0_EN") (class "Default")
      (node (ref "IC24") (pin "6") (pinfunction "EN_6") (pintype "input"))
      (node (ref "R314") (pin "2") (pinfunction "2_2") (pintype "passive"))
    )
    (net (code "21") (name "/PSU_CH_EN") (class "Default")
      (node (ref "MOD1") (pin "6") (pinfunction "PSIO0_6") (pintype "bidirectional"))
      (node (ref "R488") (pin "2") (pinfunction "2_2") (pintype "passive"))
    )
    (net (code "22") (name "/SCL_INT") (class "Default")
      (node (ref "D32") (pin "1") (pinfunction "C_1") (pintype "passive"))
      (node (ref "MOD1") (pin "11") (pinfunction "SCL_11") (pintype "bidirectional"))
      (node (ref "W11") (pin "2") (pinfunction "2_2") (pintype "bidirectional"))
    )
    (net (code "23") (name "/SDA_INT") (class "Default")
      (node (ref "D33") (pin "1") (pinfunction "C_1") (pintype "passive"))
      (node (ref "MOD1") (pin "10") (pinfunction "SDA_10") (pintype "bidirectional"))
      (node (ref "W11") (pin "3") (pinfunction "3_3") (pintype "bidirectional"))
    )
    (net (code "24") (name "/SW3") (class "Default")
      (node (ref "IC34") (pin "8") (pinfunction "VSW_8") (pintype "output"))
      (node (ref "L10") (pin "1") (pinfunction "1_1") (pintype "passive"))
    )
    (net (code "25") (name "/SW5") (class "Default")
      (node (ref "IC24") (pin "8") (pinfunction "VSW_8") (pintype "output"))
      (node (ref "L6") (pin "1") (pinfunction "1_1") (pintype "passive"))
    )
    (net (code "27") (name "GND") (class "Default")
      (node (ref "C523") (pin "2") (pinfunction "2_2") (pintype "passive"))
      (node (ref "C524") (pin "1") (pinfunction "1_1") (pintype "passive"))
      (node (ref "C525") (pin "1") (pinfunction "1_1") (pintype "passive"))
      (node (ref "C526") (pin "1") (pinfunction "1_1") (pintype "passive"))
      (node (ref "C527") (pin "2") (pinfunction "2_2") (pintype "passive"))
      (node (ref "C528") (pin "1") (pinfunction "1_1") (pintype "passive"))
      (node (ref "C529") (pin "1") (pinfunction "1_1") (pintype "passive"))
      (node (ref "C530") (pin "1") (pinfunction "1_1") (pintype "passive"))
      (node (ref "C533") (pin "1") (pinfunction "1_1") (pintype "passive"))
      (node (ref "C534") (pin "1") (pinfunction "1_1") (pintype "passive"))
      (node (ref "C536") (pin "2") (pinfunction "2_2") (pintype "passive"))
      (node (ref "C537") (pin "1") (pinfunction "1_1") (pintype "passive"))
      (node (ref "C571") (pin "1") (pinfunction "1_1") (pintype "passive"))
      (node (ref "C573") (pin "1") (pinfunction "1_1") (pintype "passive"))
      (node (ref "C575") (pin "1") (pinfunction "1_1") (pintype "passive"))
      (node (ref "C577") (pin "1") (pinfunction "1_1") (pintype "passive"))
      (node (ref "C578") (pin "1") (pinfunction "1_1") (pintype "passive"))
      (node (ref "C91") (pin "2") (pinfunction "2_2") (pintype "passive"))
      (node (ref "C92") (pin "1") (pinfunction "1_1") (pintype "passive"))
      (node (ref "C93") (pin "1") (pinfunction "1_1") (pintype "passive"))
      (node (ref "C95") (pin "1") (pinfunction "1_1") (pintype "passive"))
      (node (ref "D32") (pin "2") (pinfunction "A_2") (pintype "passive"))
      (node (ref "D33") (pin "2") (pinfunction "A_2") (pintype "passive"))
      (node (ref "IC24") (pin "1") (pinfunction "PGND_1") (pintype "power_in"))
      (node (ref "IC24") (pin "3") (pinfunction "AGND_3") (pintype "power_in"))
      (node (ref "IC34") (pin "1") (pinfunction "PGND_1") (pintype "power_in"))
      (node (ref "IC34") (pin "3") (pinfunction "AGND_3") (pintype "power_in"))
      (node (ref "IC58") (pin "12") (pinfunction "GND_12") (pintype "power_in"))
      (node (ref "IC58") (pin "21") (pinfunction "EP_21") (pintype "power_in"))
      (node (ref "IC59") (pin "12") (pinfunction "GND_12") (pintype "power_in"))
      (node (ref "IC59") (pin "21") (pinfunction "EP_21") (pintype "power_in"))
      (node (ref "LD13") (pin "1") (pinfunction "C_1") (pintype "passive"))
      (node (ref "LD22") (pin "1") (pinfunction "C_1") (pintype "passive"))
      (node (ref "LD3") (pin "1") (pinfunction "C_1") (pintype "passive"))
      (node (ref "LD7") (pin "1") (pinfunction "C_1") (pintype "passive"))
      (node (ref "LD8") (pin "1") (pinfunction "C_1") (pintype "passive"))
      (node (ref "MOD1") (pin "1") (pinfunction "GND_1") (pintype "power_in"))
      (node (ref "MOD1") (pin "14") (pinfunction "GND_14") (pintype "power_in"))
      (node (ref "MOD1") (pin "16") (pinfunction "GND_16") (pintype "power_in"))
      (node (ref "MOD1") (pin "19") (pinfunction "GND_19") (pintype "power_in"))
      (node (ref "MOD1") (pin "20") (pinfunction "GND_20") (pintype "power_in"))
      (node (ref "MOD1") (pin "21") (pinfunction "GND_21") (pintype "power_in"))
      (node (ref "MOD1") (pin "4") (pinfunction "GND_4") (pintype "power_in"))
      (node (ref "MOD1") (pin "9") (pinfunction "GND_9") (pintype "power_in"))
      (node (ref "R3") (pin "1") (pinfunction "1_1") (pintype "passive"))
      (node (ref "R314") (pin "1") (pinfunction "1_1") (pintype "passive"))
      (node (ref "R317") (pin "1") (pinfunction "1_1") (pintype "passive"))
      (node (ref "R318") (pin "2") (pinfunction "2_2") (pintype "passive"))
      (node (ref "R338") (pin "2") (pinfunction "2_2") (pintype "passive"))
      (node (ref "R480") (pin "1") (pinfunction "1_1") (pintype "passive"))
      (node (ref "R481") (pin "1") (pinfunction "1_1") (pintype "passive"))
      (node (ref "R488") (pin "1") (pinfunction "1_1") (pintype "passive"))
      (node (ref "R5") (pin "1") (pinfunction "1_1") (pintype "passive"))
      (node (ref "T16") (pin "1") (pinfunction "E_1") (pintype "passive"))
      (node (ref "T16") (pin "4") (pinfunction "E_4") (pintype "passive"))
      (node (ref "T21") (pin "2") (pinfunction "S_2") (pintype "passive"))
      (node (ref "W11") (pin "4") (pinfunction "4_4") (pintype "bidirectional"))
    )
    (net (code "28") (name "MGTAVCC") (class "Default")
      (node (ref "L27") (pin "2") (pinfunction "2_2") (pintype "passive"))
      (node (ref "L32") (pin "2") (pinfunction "2_2") (pintype "passive"))
    )
    (net (code "29") (name "MGTAVTT") (class "Default")
      (node (ref "L26") (pin "2") (pinfunction "2_2") (pintype "passive"))
    )
    (net (code "30") (name "MGTVCCAUX") (class "Default")
      (node (ref "L24") (pin "1") (pinfunction "1_1") (pintype "passive"))
    )
    (net (code "31") (name "Net-(C91-Pad1)") (class "Default")
      (node (ref "C91") (pin "1") (pinfunction "1_1") (pintype "passive"))
      (node (ref "C94") (pin "2") (pinfunction "2_2") (pintype "passive"))
      (node (ref "L36") (pin "1") (pinfunction "1_1") (pintype "passive"))
      (node (ref "L6") (pin "2") (pinfunction "2_2") (pintype "passive"))
      (node (ref "R337") (pin "2") (pinfunction "2_2") (pintype "passive"))
    )
    (net (code "32") (name "Net-(C94-Pad1)") (class "Default")
      (node (ref "C94") (pin "1") (pinfunction "1_1") (pintype "passive"))
      (node (ref "R105") (pin "2") (pinfunction "2_2") (pintype "passive"))
    )
    (net (code "33") (name "Net-(C95-Pad2)") (class "Default")
      (node (ref "C95") (pin "2") (pinfunction "2_2") (pintype "passive"))
      (node (ref "R339") (pin "1") (pinfunction "1_1") (pintype "passive"))
    )
    (net (code "34") (name "Net-(C535-Pad1)") (class "Default")
      (node (ref "C535") (pin "1") (pinfunction "1_1") (pintype "passive"))
      (node (ref "R497") (pin "2") (pinfunction "2_2") (pintype "passive"))
    )
    (net (code "35") (name "Net-(C537-Pad2)") (class "Default")
      (node (ref "C537") (pin "2") (pinfunction "2_2") (pintype "passive"))
      (node (ref "R487") (pin "1") (pinfunction "1_1") (pintype "passive"))
    )
    (net (code "36") (name "Net-(D11-A)") (class "Default")
      (node (ref "D11") (pin "2") (pinfunction "A_2") (pintype "passive"))
      (node (ref "MOD1") (pin "12") (pinfunction "EN_12") (pintype "input"))
      (node (ref "R505") (pin "1") (pinfunction "1_1") (pintype "passive"))
      (node (ref "W11") (pin "1") (pinfunction "1_1") (pintype "bidirectional"))
    )
    (net (code "37") (name "Net-(IC24-COMP)") (class "Default")
      (node (ref "IC24") (pin "5") (pinfunction "COMP_5") (pintype "input"))
      (node (ref "R339") (pin "2") (pinfunction "2_2") (pintype "passive"))
    )
    (net (code "38") (name "Net-(IC24-FB)") (class "Default")
      (node (ref "IC24") (pin "4") (pinfunction "FB_4") (pintype "input"))
      (node (ref "R105") (pin "1") (pinfunction "1_1") (pintype "passive"))
      (node (ref "R337") (pin "1") (pinfunction "1_1") (pintype "passive"))
      (node (ref "R338") (pin "1") (pinfunction "1_1") (pintype "passive"))
    )
    (net (code "39") (name "Net-(IC34-COMP)") (class "Default")
      (node (ref "IC34") (pin "5") (pinfunction "COMP_5") (pintype "input"))
      (node (ref "R487") (pin "2") (pinfunction "2_2") (pintype "passive"))
    )
    (net (code "40") (name "Net-(IC34-FB)") (class "Default")
      (node (ref "IC34") (pin "4") (pinfunction "FB_4") (pintype "input"))
      (node (ref "R316") (pin "1") (pinfunction "1_1") (pintype "passive"))
      (node (ref "R318") (pin "1") (pinfunction "1_1") (pintype "passive"))
      (node (ref "R497") (pin "1") (pinfunction "1_1") (pintype "passive"))
    )
    (net (code "41") (name "Net-(IC58-FB)") (class "Default")
      (node (ref "IC58") (pin "16") (pinfunction "FB_16") (pintype "output"))
      (node (ref "R5") (pin "2") (pinfunction "2_2") (pintype "passive"))
      (node (ref "R500") (pin "1") (pinfunction "1_1") (pintype "passive"))
    )
    (net (code "42") (name "Net-(IC58-SS)") (class "Default")
      (node (ref "C523") (pin "1") (pinfunction "1_1") (pintype "passive"))
      (node (ref "IC58") (pin "15") (pinfunction "SS_15") (pintype "passive"))
    )
    (net (code "43") (name "Net-(IC59-FB)") (class "Default")
      (node (ref "IC59") (pin "16") (pinfunction "FB_16") (pintype "output"))
      (node (ref "R3") (pin "2") (pinfunction "2_2") (pintype "passive"))
      (node (ref "R4") (pin "1") (pinfunction "1_1") (pintype "passive"))
    )
    (net (code "44") (name "Net-(IC59-SS)") (class "Default")
      (node (ref "C527") (pin "1") (pinfunction "1_1") (pintype "passive"))
      (node (ref "IC59") (pin "15") (pinfunction "SS_15") (pintype "passive"))
    )
    (net (code "45") (name "Net-(LD3-A)") (class "Default")
      (node (ref "LD3") (pin "2") (pinfunction "A_2") (pintype "passive"))
      (node (ref "R94") (pin "1") (pinfunction "1_1") (pintype "passive"))
    )
    (net (code "46") (name "Net-(LD4-A)") (class "Default")
      (node (ref "LD4") (pin "2") (pinfunction "A_2") (pintype "passive"))
      (node (ref "R501") (pin "1") (pinfunction "1_1") (pintype "passive"))
    )
    (net (code "47") (name "Net-(LD4-C)") (class "Default")
      (node (ref "LD4") (pin "1") (pinfunction "C_1") (pintype "passive"))
      (node (ref "T16") (pin "6") (pinfunction "C_6") (pintype "passive"))
    )
    (net (code "48") (name "Net-(LD5-A)") (class "Default")
      (node (ref "LD5") (pin "2") (pinfunction "A_2") (pintype "passive"))
      (node (ref "R502") (pin "1") (pinfunction "1_1") (pintype "passive"))
    )
    (net (code "49") (name "Net-(LD5-C)") (class "Default")
      (node (ref "LD5") (pin "1") (pinfunction "C_1") (pintype "passive"))
      (node (ref "T16") (pin "3") (pinfunction "C_3") (pintype "passive"))
    )
    (net (code "50") (name "Net-(LD6-A)") (class "Default")
      (node (ref "LD6") (pin "2") (pinfunction "A_2") (pintype "passive"))
      (node (ref "R503") (pin "1") (pinfunction "1_1") (pintype "passive"))
    )
    (net (code "51") (name "Net-(LD6-C)") (class "Default")
      (node (ref "LD6") (pin "1") (pinfunction "C_1") (pintype "passive"))
      (node (ref "T21") (pin "3") (pinfunction "D_3") (pintype "passive"))
    )
    (net (code "52") (name "Net-(LD7-A)") (class "Default")
      (node (ref "LD7") (pin "2") (pinfunction "A_2") (pintype "passive"))
      (node (ref "R504") (pin "1") (pinfunction "1_1") (pintype "passive"))
    )
    (net (code "53") (name "Net-(LD8-A)") (class "Default")
      (node (ref "LD8") (pin "2") (pinfunction "A_2") (pintype "passive"))
      (node (ref "R506") (pin "1") (pinfunction "1_1") (pintype "passive"))
    )
    (net (code "54") (name "Net-(LD13-A)") (class "Default")
      (node (ref "LD13") (pin "2") (pinfunction "A_2") (pintype "passive"))
      (node (ref "R484") (pin "1") (pinfunction "1_1") (pintype "passive"))
    )
    (net (code "55") (name "Net-(LD22-A)") (class "Default")
      (node (ref "LD22") (pin "2") (pinfunction "A_2") (pintype "passive"))
      (node (ref "R315") (pin "1") (pinfunction "1_1") (pintype "passive"))
    )
    (net (code "56") (name "Net-(T16A-B)") (class "Default")
      (node (ref "R482") (pin "2") (pinfunction "2_2") (pintype "passive"))
      (node (ref "T16") (pin "2") (pinfunction "B_2") (pintype "passive"))
    )
    (net (code "57") (name "Net-(T16B-B)") (class "Default")
      (node (ref "R489") (pin "2") (pinfunction "2_2") (pintype "passive"))
      (node (ref "T16") (pin "5") (pinfunction "B_5") (pintype "passive"))
    )
    (net (code "58") (name "P0V95") (class "Default")
      (node (ref "R482") (pin "1") (pinfunction "1_1") (pintype "passive"))
      (node (ref "TP8") (pin "1") (pinfunction "1_1") (pintype "bidirectional"))
    )
    (net (code "59") (name "P0V95B") (class "Default")
      (node (ref "C525") (pin "2") (pinfunction "2_2") (pintype "passive"))
      (node (ref "IC58") (pin "1") (pinfunction "OUT_1") (pintype "power_in"))
      (node (ref "IC58") (pin "18") (pinfunction "OUT_18") (pintype "power_in"))
      (node (ref "IC58") (pin "19") (pinfunction "OUT_19") (pintype "power_in"))
      (node (ref "IC58") (pin "20") (pinfunction "OUT_20") (pintype "power_in"))
      (node (ref "L25") (pin "1") (pinfunction "1_1") (pintype "passive"))
      (node (ref "R500") (pin "2") (pinfunction "2_2") (pintype "passive"))
    )
    (net (code "60") (name "P1V0") (class "Default")
      (node (ref "C526") (pin "2") (pinfunction "2_2") (pintype "passive"))
      (node (ref "IC58") (pin "5") (pinfunction "IN_5") (pintype "input"))
      (node (ref "IC58") (pin "6") (pinfunction "IN_6") (pintype "input"))
      (node (ref "IC58") (pin "7") (pinfunction "IN_7") (pintype "input"))
      (node (ref "IC58") (pin "8") (pinfunction "IN_8") (pintype "input"))
      (node (ref "L23") (pin "1") (pinfunction "1_1") (pintype "passive"))
    )
    (net (code "61") (name "P1V2") (class "Default")
      (node (ref "C529") (pin "2") (pinfunction "2_2") (pintype "passive"))
      (node (ref "IC59") (pin "1") (pinfunction "OUT_1") (pintype "power_in"))
      (node (ref "IC59") (pin "18") (pinfunction "OUT_18") (pintype "power_in"))
      (node (ref "IC59") (pin "19") (pinfunction "OUT_19") (pintype "power_in"))
      (node (ref "IC59") (pin "20") (pinfunction "OUT_20") (pintype "power_in"))
      (node (ref "L26") (pin "1") (pinfunction "1_1") (pintype "passive"))
      (node (ref "R4") (pin "2") (pinfunction "2_2") (pintype "passive"))
      (node (ref "TP12") (pin "1") (pinfunction "1_1") (pintype "bidirectional"))
    )
    (net (code "62") (name "P1V5") (class "Default")
      (node (ref "L22") (pin "2") (pinfunction "2_2") (pintype "passive"))
      (node (ref "L31") (pin "2") (pinfunction "2_2") (pintype "passive"))
      (node (ref "L35") (pin "2") (pinfunction "2_2") (pintype "passive"))
      (node (ref "R489") (pin "1") (pinfunction "1_1") (pintype "passive"))
      (node (ref "TP9") (pin "1") (pinfunction "1_1") (pintype "bidirectional"))
    )
    (net (code "63") (name "P1V8") (class "Default")
      (node (ref "L24") (pin "2") (pinfunction "2_2") (pintype "passive"))
      (node (ref "L29") (pin "2") (pinfunction "2_2") (pintype "passive"))
      (node (ref "L30") (pin "1") (pinfunction "1_1") (pintype "passive"))
      (node (ref "L33") (pin "2") (pinfunction "2_2") (pintype "passive"))
      (node (ref "T21") (pin "1") (pinfunction "G_1") (pintype "passive"))
      (node (ref "TP10") (pin "1") (pinfunction "1_1") (pintype "bidirectional"))
    )
    (net (code "64") (name "P3V3") (class "Default")
      (node (ref "L28") (pin "2") (pinfunction "2_2") (pintype "passive"))
      (node (ref "L34") (pin "2") (pinfunction "2_2") (pintype "passive"))
      (node (ref "R506") (pin "2") (pinfunction "2_2") (pintype "passive"))
      (node (ref "TP11") (pin "1") (pinfunction "1_1") (pintype "bidirectional"))
    )
    (net (code "65") (name "P3V3MP") (class "Default")
      (node (ref "D11") (pin "1") (pinfunction "C_1") (pintype "passive"))
      (node (ref "MOD1") (pin "5") (pinfunction "P3V3_IN_5") (pintype "power_in"))
      (node (ref "R490") (pin "2") (pinfunction "2_2") (pintype "passive"))
      (node (ref "R491") (pin "2") (pinfunction "2_2") (pintype "passive"))
      (node (ref "R495") (pin "1") (pinfunction "1_1") (pintype "passive"))
      (node (ref "R496") (pin "1") (pinfunction "1_1") (pintype "passive"))
      (node (ref "R94") (pin "2") (pinfunction "2_2") (pintype "passive"))
    )
    (net (code "66") (name "P3V3_FMC") (class "Default")
      (node (ref "C535") (pin "2") (pinfunction "2_2") (pintype "passive"))
      (node (ref "C536") (pin "1") (pinfunction "1_1") (pintype "passive"))
      (node (ref "L10") (pin "2") (pinfunction "2_2") (pintype "passive"))
      (node (ref "R315") (pin "2") (pinfunction "2_2") (pintype "passive"))
      (node (ref "R316") (pin "2") (pinfunction "2_2") (pintype "passive"))
      (node (ref "TP17") (pin "1") (pinfunction "1_1") (pintype "bidirectional"))
    )
    (net (code "67") (name "P5V0") (class "Default")
      (node (ref "C524") (pin "2") (pinfunction "2_2") (pintype "passive"))
      (node (ref "C528") (pin "2") (pinfunction "2_2") (pintype "passive"))
      (node (ref "C578") (pin "2") (pinfunction "2_2") (pintype "passive"))
      (node (ref "IC58") (pin "10") (pinfunction "BIAS_10") (pintype "input"))
      (node (ref "IC59") (pin "10") (pinfunction "BIAS_10") (pintype "input"))
      (node (ref "L36") (pin "2") (pinfunction "2_2") (pintype "passive"))
      (node (ref "R484") (pin "2") (pinfunction "2_2") (pintype "passive"))
      (node (ref "TP7") (pin "1") (pinfunction "1_1") (pintype "bidirectional"))
    )
    (net (code "68") (name "P12V0") (class "Default")
      (node (ref "C533") (pin "2") (pinfunction "2_2") (pintype "passive"))
      (node (ref "C534") (pin "2") (pinfunction "2_2") (pintype "passive"))
      (node (ref "C92") (pin "2") (pinfunction "2_2") (pintype "passive"))
      (node (ref "C93") (pin "2") (pinfunction "2_2") (pintype "passive"))
      (node (ref "IC24") (pin "2") (pinfunction "VIN_2") (pintype "input"))
      (node (ref "IC34") (pin "2") (pinfunction "VIN_2") (pintype "input"))
      (node (ref "MOD1") (pin "15") (pinfunction "VIN_15") (pintype "input"))
      (node (ref "R501") (pin "2") (pinfunction "2_2") (pintype "passive"))
      (node (ref "R502") (pin "2") (pinfunction "2_2") (pintype "passive"))
      (node (ref "R503") (pin "2") (pinfunction "2_2") (pintype "passive"))
      (node (ref "R504") (pin "2") (pinfunction "2_2") (pintype "passive"))
    )
    (net (code "69") (name "VCCAUX") (class "Default")
      (node (ref "L30") (pin "2") (pinfunction "2_2") (pintype "passive"))
    )
    (net (code "70") (name "VCCBRAM") (class "Default")
      (node (ref "L25") (pin "2") (pinfunction "2_2") (pintype "passive"))
      (node (ref "R554") (pin "2") (pinfunction "2_2") (pintype "passive"))
    )
    (net (code "71") (name "VCCINT") (class "Default")
      (node (ref "R554") (pin "1") (pinfunction "1_1") (pintype "passive"))
      (node (ref "TP13") (pin "1") (pinfunction "1_1") (pintype "bidirectional"))
    )
    (net (code "72") (name "unconnected-(IC58-NC-Pad2)") (class "Default")
      (node (ref "IC58") (pin "2") (pinfunction "NC_2") (pintype "passive"))
    )
    (net (code "73") (name "unconnected-(IC58-NC-Pad3)") (class "Default")
      (node (ref "IC58") (pin "3") (pinfunction "NC_3") (pintype "passive"))
    )
    (net (code "74") (name "unconnected-(IC58-NC-Pad4)") (class "Default")
      (node (ref "IC58") (pin "4") (pinfunction "NC_4") (pintype "passive"))
    )
    (net (code "75") (name "unconnected-(IC58-NC-Pad13)") (class "Default")
      (node (ref "IC58") (pin "13") (pinfunction "NC_13") (pintype "passive"))
    )
    (net (code "76") (name "unconnected-(IC58-NC-Pad14)") (class "Default")
      (node (ref "IC58") (pin "14") (pinfunction "NC_14") (pintype "passive"))
    )
    (net (code "77") (name "unconnected-(IC58-NC-Pad17)") (class "Default")
      (node (ref "IC58") (pin "17") (pinfunction "NC_17") (pintype "passive"))
    )
    (net (code "78") (name "unconnected-(IC59-NC-Pad2)") (class "Default")
      (node (ref "IC59") (pin "2") (pinfunction "NC_2") (pintype "passive"))
    )
    (net (code "79") (name "unconnected-(IC59-NC-Pad3)") (class "Default")
      (node (ref "IC59") (pin "3") (pinfunction "NC_3") (pintype "passive"))
    )
    (net (code "80") (name "unconnected-(IC59-NC-Pad4)") (class "Default")
      (node (ref "IC59") (pin "4") (pinfunction "NC_4") (pintype "passive"))
    )
    (net (code "81") (name "unconnected-(IC59-NC-Pad13)") (class "Default")
      (node (ref "IC59") (pin "13") (pinfunction "NC_13") (pintype "passive"))
    )
    (net (code "82") (name "unconnected-(IC59-NC-Pad14)") (class "Default")
      (node (ref "IC59") (pin "14") (pinfunction "NC_14") (pintype "passive"))
    )
    (net (code "83") (name "unconnected-(IC59-NC-Pad17)") (class "Default")
      (node (ref "IC59") (pin "17") (pinfunction "NC_17") (pintype "passive"))
    )
  )
)
